# untitled.net
KiCad netlist of a schematic drawn in EAGLE
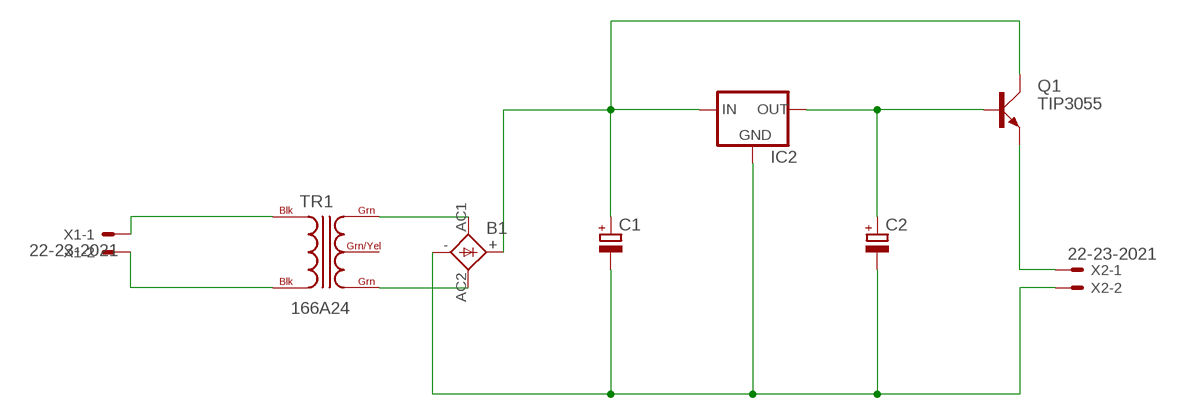
[diagram p0: schematic, sheet 1]

(export (version "E")
  (design (tool "Eeschema 10.0.6"))
  (components
    (comp (ref "B1")
      (value "FB32")
      (footprint "eagle-import:FB32")
      (libsource (lib "eagle-import") (part "FB32"))
    )
    (comp (ref "C1")
      (value "CPOL-EUE7.5-16")
      (footprint "eagle-import:E7,5-16")
      (libsource (lib "eagle-import") (part "CPOL-EUE7.5-16"))
    )
    (comp (ref "C2")
      (value "CPOL-EUE3.5-8")
      (footprint "eagle-import:E3,5-8")
      (libsource (lib "eagle-import") (part "CPOL-EUE3.5-8"))
    )
    (comp (ref "IC2")
      (value "78XXL")
      (footprint "eagle-import:78XXL")
      (libsource (lib "eagle-import") (part "78XXL"))
    )
    (comp (ref "Q1")
      (value "TIP3055")
      (footprint "eagle-import:TOP3AV")
      (libsource (lib "eagle-import") (part "TIP3055"))
    )
    (comp (ref "TR1")
      (value "166A24")
      (footprint "eagle-import:C2H")
      (libsource (lib "eagle-import") (part "166A24"))
    )
    (comp (ref "X1")
      (value "22-23-2021")
      (footprint "eagle-import:22-23-2021")
      (fields (field (name "MF") "MOLEX"))
      (libsource (lib "eagle-import") (part "22-23-2021"))
    )
    (comp (ref "X2")
      (value "22-23-2021")
      (footprint "eagle-import:22-23-2021")
      (fields (field (name "MF") "MOLEX"))
      (libsource (lib "eagle-import") (part "22-23-2021"))
    )
  )
  (nets
    (net (code "1") (name "Net-(B1-Pad+)") (class "Default")
      (node (ref "B1") (pin "+") (pinfunction "+_+") (pintype "passive"))
      (node (ref "C1") (pin "+") (pinfunction "+_+") (pintype "passive"))
      (node (ref "IC2") (pin "IN") (pinfunction "IN_IN") (pintype "input"))
      (node (ref "Q1") (pin "C") (pinfunction "C_C") (pintype "passive"))
    )
    (net (code "2") (name "Net-(B1-PadAC1)") (class "Default")
      (node (ref "B1") (pin "AC1") (pinfunction "AC1_AC1") (pintype "passive"))
      (node (ref "TR1") (pin "GRN@1") (pinfunction "GRN_GRN@1") (pintype "passive"))
    )
    (net (code "3") (name "Net-(B1-PadAC2)") (class "Default")
      (node (ref "B1") (pin "AC2") (pinfunction "AC2_AC2") (pintype "passive"))
      (node (ref "TR1") (pin "GRN@2") (pinfunction "GRN_GRN@2") (pintype "passive"))
    )
    (net (code "4") (name "Net-(C2-Pad+)") (class "Default")
      (node (ref "C2") (pin "+") (pinfunction "+_+") (pintype "passive"))
      (node (ref "IC2") (pin "OUT") (pinfunction "OUT_OUT") (pintype "passive"))
      (node (ref "Q1") (pin "B") (pinfunction "B_B") (pintype "passive"))
    )
    (net (code "5") (name "Net-(X1A-S)") (class "Default")
      (node (ref "TR1") (pin "BLK@1") (pinfunction "BLK_BLK@1") (pintype "passive"))
      (node (ref "X1") (pin "1") (pinfunction "S_1") (pintype "passive"))
    )
    (net (code "6") (name "Net-(X1B-S)") (class "Default")
      (node (ref "TR1") (pin "BLK@2") (pinfunction "BLK_BLK@2") (pintype "passive"))
      (node (ref "X1") (pin "2") (pinfunction "S_2") (pintype "passive"))
    )
    (net (code "7") (name "Net-(X2A-S)") (class "Default")
      (node (ref "Q1") (pin "E") (pinfunction "E_E") (pintype "passive"))
      (node (ref "X2") (pin "1") (pinfunction "S_1") (pintype "passive"))
    )
    (net (code "8") (name "Net-(X2B-S)") (class "Default")
      (node (ref "B1") (pin "-") (pinfunction "-_-") (pintype "passive"))
      (node (ref "C1") (pin "-") (pinfunction "-_-") (pintype "passive"))
      (node (ref "C2") (pin "-") (pinfunction "-_-") (pintype "passive"))
      (node (ref "IC2") (pin "GND") (pinfunction "GND_GND") (pintype "input"))
      (node (ref "X2") (pin "2") (pinfunction "S_2") (pintype "passive"))
    )
    (net (code "9") (name "unconnected-(TR1-PadGRN{slash}YEL)") (class "Default")
      (node (ref "TR1") (pin "GRN/YEL") (pinfunction "GRN/YEL_GRN/YEL") (pintype "passive"))
    )
  )
)
